# Gondola_Sail_electronics_M4.net
KiCad netlist of a schematic drawn in EAGLE
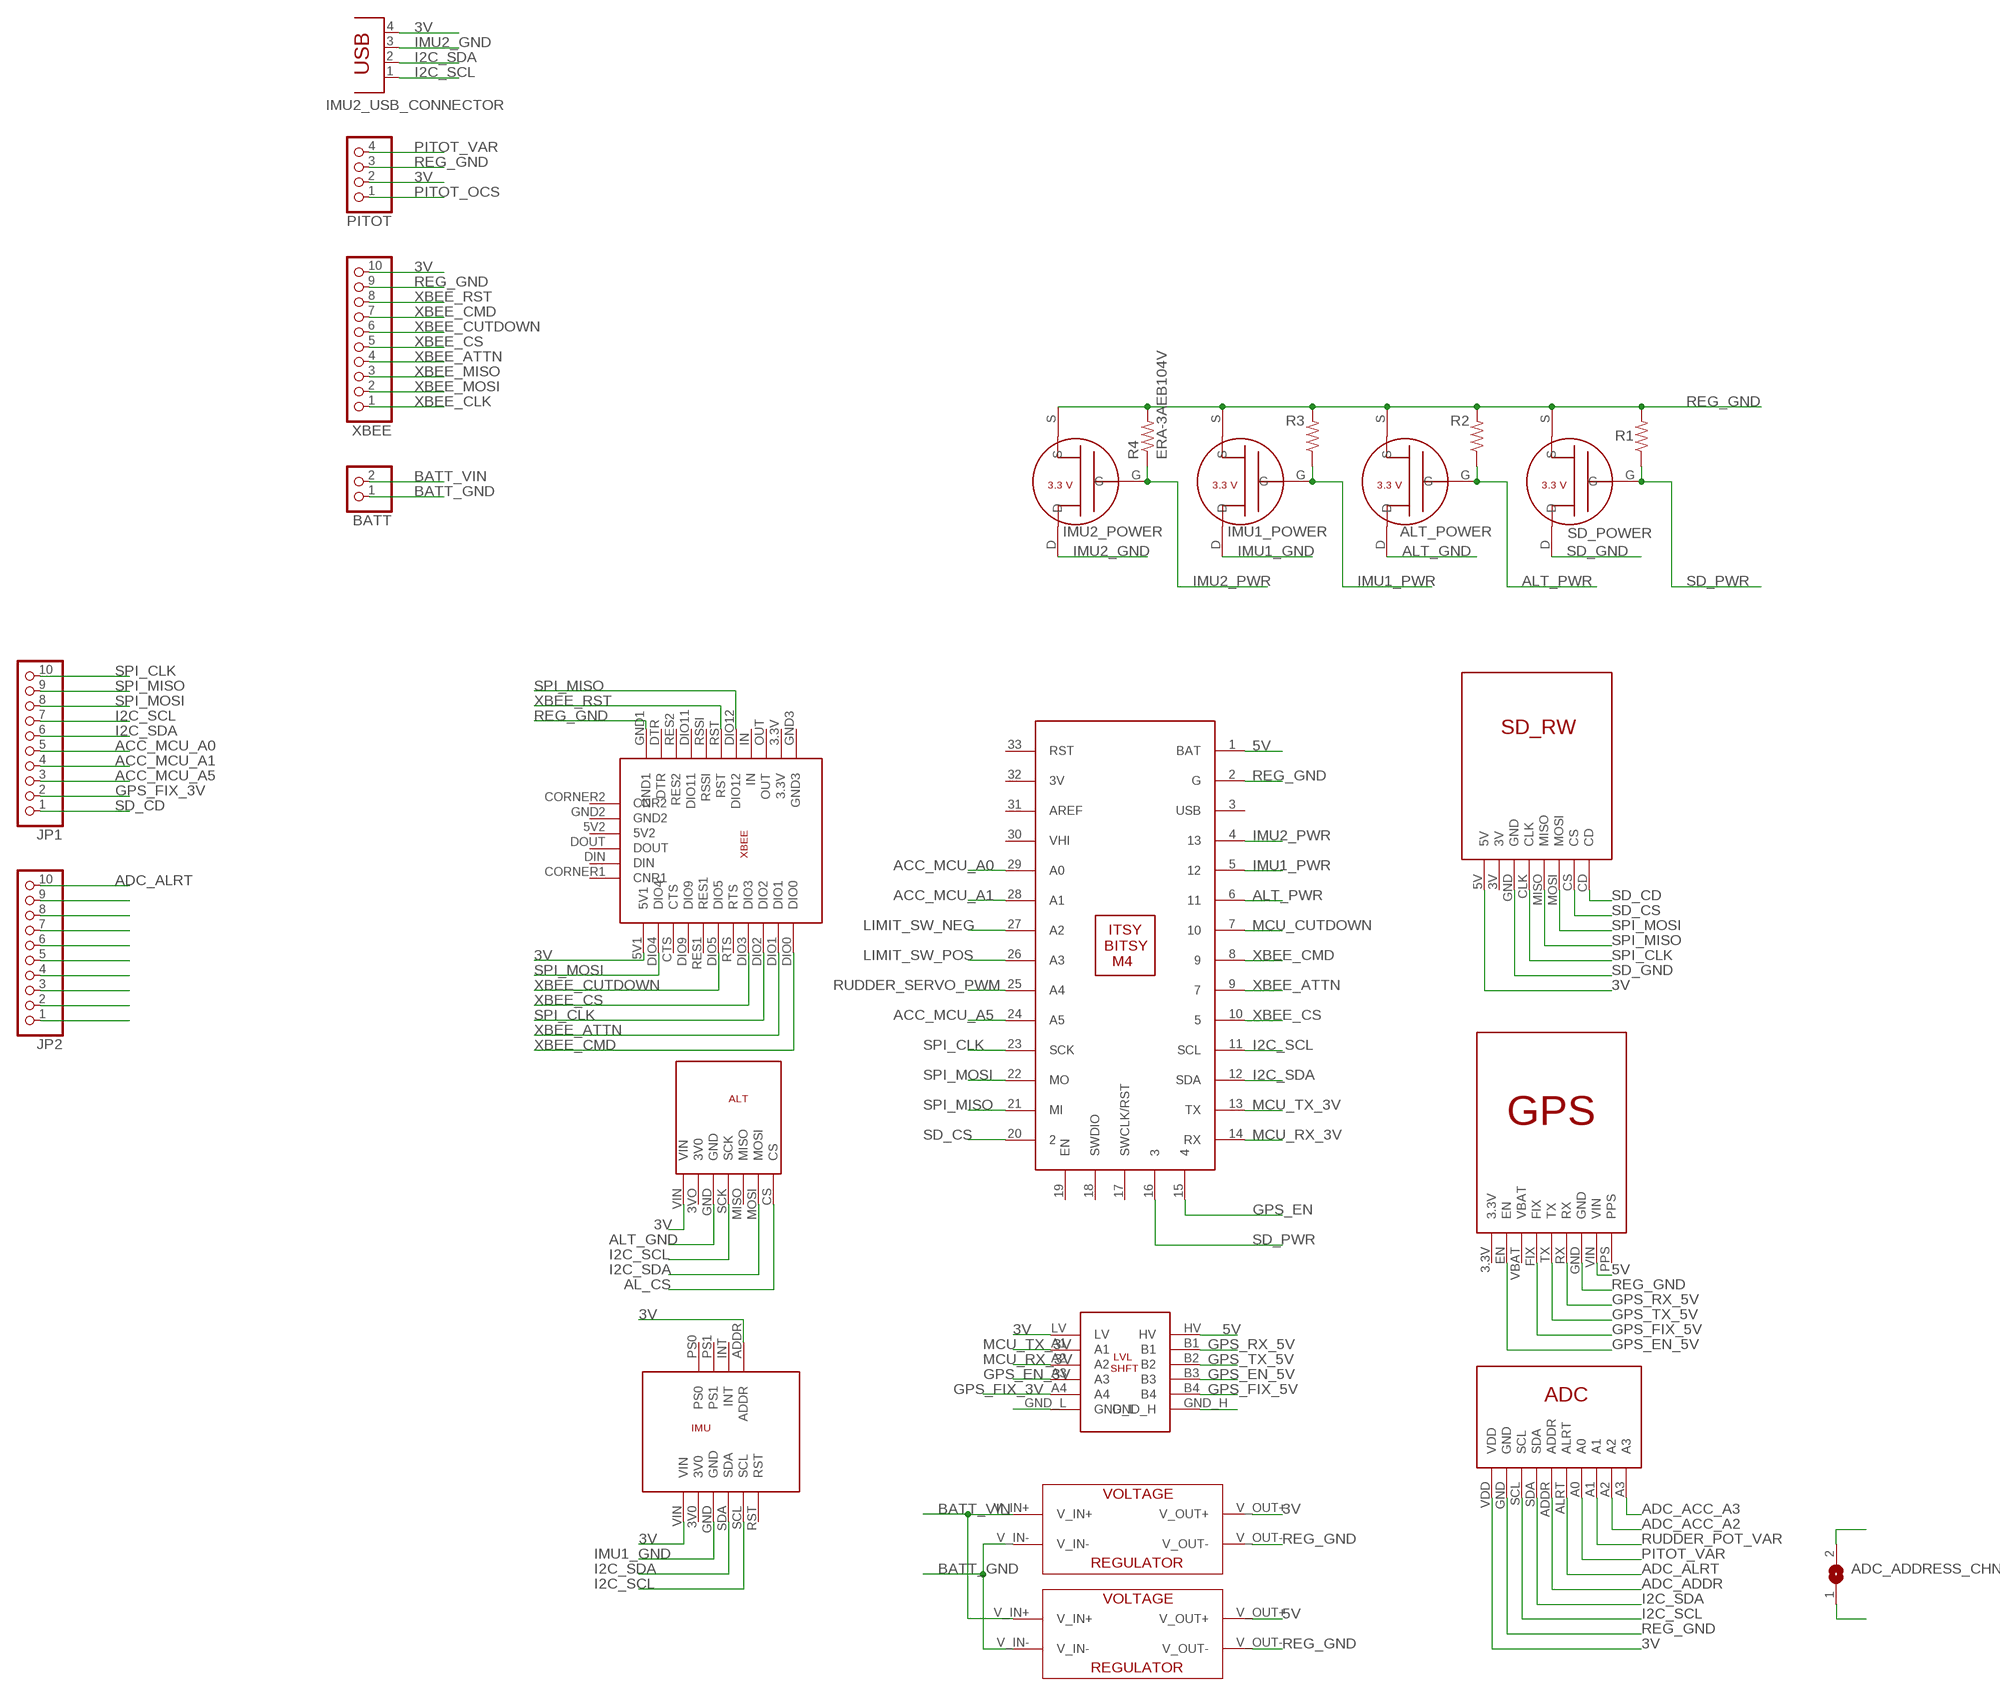
[diagram p0: schematic, sheet 1]

(export (version "E")
  (design (tool "Eeschema 10.0.6"))
  (components
    (comp (ref "3V_REG")
      (value "3V/5V_REGULATOR")
      (footprint "eagle-import:5V_3V_REGULATOR")
      (libsource (lib "eagle-import") (part "3V/5V_REGULATOR"))
    )
    (comp (ref "5V_REG")
      (value "3V/5V_REGULATOR")
      (footprint "eagle-import:5V_3V_REGULATOR")
      (libsource (lib "eagle-import") (part "3V/5V_REGULATOR"))
    )
    (comp (ref "ADC_ADDRESS_CHNG")
      (value "SJ")
      (footprint "eagle-import:SJ")
      (libsource (lib "eagle-import") (part "SJ"))
    )
    (comp (ref "ALT_POWER")
      (value "3.3V_NCH_FET")
      (footprint "eagle-import:3.3VTRANSISTOR")
      (libsource (lib "eagle-import") (part "3.3V_NCH_FET"))
    )
    (comp (ref "BATT")
      (value "PINHD-1X2/90")
      (footprint "eagle-import:1X02_90")
      (libsource (lib "eagle-import") (part "PINHD-1X2/90"))
    )
    (comp (ref "IMU1")
      (value "BNO055")
      (footprint "eagle-import:BNO055")
      (libsource (lib "eagle-import") (part "BNO055"))
    )
    (comp (ref "IMU1_POWER")
      (value "3.3V_NCH_FET")
      (footprint "eagle-import:3.3VTRANSISTOR")
      (libsource (lib "eagle-import") (part "3.3V_NCH_FET"))
    )
    (comp (ref "IMU2_POWER")
      (value "3.3V_NCH_FET")
      (footprint "eagle-import:3.3VTRANSISTOR")
      (libsource (lib "eagle-import") (part "3.3V_NCH_FET"))
    )
    (comp (ref "IMU2_USB_CONNECTOR")
      (value "PN87520")
      (footprint "eagle-import:PN87520")
      (libsource (lib "eagle-import") (part "PN87520"))
    )
    (comp (ref "JP1")
      (value "PINHD-1X10/90")
      (footprint "eagle-import:1X10_90")
      (libsource (lib "eagle-import") (part "PINHD-1X10/90"))
    )
    (comp (ref "JP2")
      (value "PINHD-1X10/90")
      (footprint "eagle-import:1X10_90")
      (libsource (lib "eagle-import") (part "PINHD-1X10/90"))
    )
    (comp (ref "PITOT")
      (value "PINHD-1X4/90")
      (footprint "eagle-import:1X04_90")
      (libsource (lib "eagle-import") (part "PINHD-1X4/90"))
    )
    (comp (ref "R1")
      (value "ERA-3AEB104V")
      (footprint "eagle-import:RESC1608X55")
      (fields (field (name "DIGI-KEY_PART_NUMBER") "P100KDBCT-ND") (field (name "MF") "Panasonic"))
      (libsource (lib "eagle-import") (part "ERA-3AEB104V"))
    )
    (comp (ref "R2")
      (value "ERA-3AEB104V")
      (footprint "eagle-import:RESC1608X55")
      (fields (field (name "DIGI-KEY_PART_NUMBER") "P100KDBCT-ND") (field (name "MF") "Panasonic"))
      (libsource (lib "eagle-import") (part "ERA-3AEB104V"))
    )
    (comp (ref "R3")
      (value "ERA-3AEB104V")
      (footprint "eagle-import:RESC1608X55")
      (fields (field (name "DIGI-KEY_PART_NUMBER") "P100KDBCT-ND") (field (name "MF") "Panasonic"))
      (libsource (lib "eagle-import") (part "ERA-3AEB104V"))
    )
    (comp (ref "R4")
      (value "ERA-3AEB104V")
      (footprint "eagle-import:RESC1608X55")
      (fields (field (name "DIGI-KEY_PART_NUMBER") "P100KDBCT-ND") (field (name "MF") "Panasonic"))
      (libsource (lib "eagle-import") (part "ERA-3AEB104V"))
    )
    (comp (ref "SD_POWER")
      (value "3.3V_NCH_FET")
      (footprint "eagle-import:3.3VTRANSISTOR")
      (libsource (lib "eagle-import") (part "3.3V_NCH_FET"))
    )
    (comp (ref "U$1")
      (value "ADAFRUIT_GPS")
      (footprint "eagle-import:ADAFRUIT_GPS")
      (libsource (lib "eagle-import") (part "ADAFRUIT_GPS"))
    )
    (comp (ref "U$2")
      (value "ADAFRUI_SD_RW")
      (footprint "eagle-import:ADAFRUIT_SD_RW")
      (libsource (lib "eagle-import") (part "ADAFRUI_SD_RW"))
    )
    (comp (ref "U$3")
      (value "ADS1115")
      (footprint "eagle-import:ADS1115")
      (libsource (lib "eagle-import") (part "ADS1115"))
    )
    (comp (ref "U$4")
      (value "BME280")
      (footprint "eagle-import:BME280")
      (libsource (lib "eagle-import") (part "BME280"))
    )
    (comp (ref "U$6")
      (value "BSS138_LVLSHIFT")
      (footprint "eagle-import:BSS138_LEVELSHIFT")
      (libsource (lib "eagle-import") (part "BSS138_LVLSHIFT"))
    )
    (comp (ref "U$7")
      (value "XBEE_XPLORER_REG")
      (footprint "eagle-import:XBEE_EXPLORER_REG'D")
      (libsource (lib "eagle-import") (part "XBEE_XPLORER_REG"))
    )
    (comp (ref "U$8")
      (value "ITSY_BITSY_M4")
      (footprint "eagle-import:ITSY_BITSY_M4")
      (libsource (lib "eagle-import") (part "ITSY_BITSY_M4"))
    )
    (comp (ref "XBEE")
      (value "PINHD-1X10/90")
      (footprint "eagle-import:1X10_90")
      (libsource (lib "eagle-import") (part "PINHD-1X10/90"))
    )
  )
  (nets
    (net (code "1") (name "/3V") (class "Default")
      (node (ref "3V_REG") (pin "V_OUT+") (pinfunction "V_OUT+_V_OUT+") (pintype "bidirectional"))
      (node (ref "IMU1") (pin "ADDR") (pinfunction "ADDR_ADDR") (pintype "bidirectional"))
      (node (ref "IMU1") (pin "VIN") (pinfunction "VIN_VIN") (pintype "bidirectional"))
      (node (ref "IMU2_USB_CONNECTOR") (pin "4") (pinfunction "4_4") (pintype "passive"))
      (node (ref "PITOT") (pin "2") (pinfunction "2_2") (pintype "passive"))
      (node (ref "U$2") (pin "5V") (pinfunction "5V_5V") (pintype "bidirectional"))
      (node (ref "U$3") (pin "VDD") (pinfunction "VDD_VDD") (pintype "bidirectional"))
      (node (ref "U$4") (pin "VIN") (pinfunction "VIN_VIN") (pintype "bidirectional"))
      (node (ref "U$6") (pin "LV") (pinfunction "LV_LV") (pintype "bidirectional"))
      (node (ref "U$7") (pin "5V1") (pinfunction "5V1_5V1") (pintype "bidirectional"))
      (node (ref "XBEE") (pin "10") (pinfunction "10_10") (pintype "passive"))
    )
    (net (code "2") (name "/5V") (class "Default")
      (node (ref "5V_REG") (pin "V_OUT+") (pinfunction "V_OUT+_V_OUT+") (pintype "bidirectional"))
      (node (ref "U$1") (pin "VIN") (pinfunction "VIN_VIN") (pintype "bidirectional"))
      (node (ref "U$6") (pin "HV") (pinfunction "HV_HV") (pintype "bidirectional"))
      (node (ref "U$8") (pin "1") (pinfunction "BAT_1") (pintype "output"))
    )
    (net (code "3") (name "/ACC_MCU_A0") (class "Default")
      (node (ref "JP1") (pin "5") (pinfunction "5_5") (pintype "passive"))
      (node (ref "U$8") (pin "29") (pinfunction "A0_29") (pintype "bidirectional"))
    )
    (net (code "4") (name "/ACC_MCU_A1") (class "Default")
      (node (ref "JP1") (pin "4") (pinfunction "4_4") (pintype "passive"))
      (node (ref "U$8") (pin "28") (pinfunction "A1_28") (pintype "bidirectional"))
    )
    (net (code "5") (name "/ACC_MCU_A5") (class "Default")
      (node (ref "JP1") (pin "3") (pinfunction "3_3") (pintype "passive"))
      (node (ref "U$8") (pin "24") (pinfunction "A5_24") (pintype "bidirectional"))
    )
    (net (code "6") (name "/ADC_ACC_A2") (class "Default")
      (node (ref "U$3") (pin "A2") (pinfunction "A2_A2") (pintype "bidirectional"))
    )
    (net (code "7") (name "/ADC_ACC_A3") (class "Default")
      (node (ref "U$3") (pin "A3") (pinfunction "A3_A3") (pintype "bidirectional"))
    )
    (net (code "8") (name "/ADC_ADDR") (class "Default")
      (node (ref "U$3") (pin "ADDR") (pinfunction "ADDR_ADDR") (pintype "bidirectional"))
    )
    (net (code "9") (name "/ADC_ALRT") (class "Default")
      (node (ref "JP2") (pin "10") (pinfunction "10_10") (pintype "passive"))
      (node (ref "U$3") (pin "ALRT") (pinfunction "ALRT_ALRT") (pintype "bidirectional"))
    )
    (net (code "10") (name "/ALT_GND") (class "Default")
      (node (ref "ALT_POWER") (pin "D") (pinfunction "D_D") (pintype "bidirectional"))
      (node (ref "U$4") (pin "GND") (pinfunction "GND_GND") (pintype "bidirectional"))
    )
    (net (code "11") (name "/ALT_PWR") (class "Default")
      (node (ref "ALT_POWER") (pin "G") (pinfunction "G_G") (pintype "bidirectional"))
      (node (ref "R2") (pin "1") (pinfunction "1_1") (pintype "passive"))
      (node (ref "U$8") (pin "6") (pinfunction "11_6") (pintype "bidirectional"))
    )
    (net (code "12") (name "/AL_CS") (class "Default")
      (node (ref "U$4") (pin "CS") (pinfunction "CS_CS") (pintype "bidirectional"))
    )
    (net (code "13") (name "/BATT_GND") (class "Default")
      (node (ref "3V_REG") (pin "V_IN-") (pinfunction "V_IN-_V_IN-") (pintype "bidirectional"))
      (node (ref "5V_REG") (pin "V_IN-") (pinfunction "V_IN-_V_IN-") (pintype "bidirectional"))
      (node (ref "BATT") (pin "1") (pinfunction "1_1") (pintype "passive"))
    )
    (net (code "14") (name "/BATT_VIN") (class "Default")
      (node (ref "3V_REG") (pin "V_IN+") (pinfunction "V_IN+_V_IN+") (pintype "bidirectional"))
      (node (ref "5V_REG") (pin "V_IN+") (pinfunction "V_IN+_V_IN+") (pintype "bidirectional"))
      (node (ref "BATT") (pin "2") (pinfunction "2_2") (pintype "passive"))
    )
    (net (code "15") (name "/GPS_EN") (class "Default")
      (node (ref "U$8") (pin "15") (pinfunction "4_15") (pintype "bidirectional"))
    )
    (net (code "16") (name "/GPS_EN_3V") (class "Default")
      (node (ref "U$6") (pin "A3") (pinfunction "A3_A3") (pintype "bidirectional"))
    )
    (net (code "17") (name "/GPS_EN_5V") (class "Default")
      (node (ref "U$1") (pin "EN") (pinfunction "EN_EN") (pintype "bidirectional"))
      (node (ref "U$6") (pin "B3") (pinfunction "B3_B3") (pintype "bidirectional"))
    )
    (net (code "18") (name "/GPS_FIX_3V") (class "Default")
      (node (ref "JP1") (pin "2") (pinfunction "2_2") (pintype "passive"))
      (node (ref "U$6") (pin "A4") (pinfunction "A4_A4") (pintype "bidirectional"))
    )
    (net (code "19") (name "/GPS_FIX_5V") (class "Default")
      (node (ref "U$1") (pin "FIX") (pinfunction "FIX_FIX") (pintype "bidirectional"))
      (node (ref "U$6") (pin "B4") (pinfunction "B4_B4") (pintype "bidirectional"))
    )
    (net (code "20") (name "/GPS_RX_5V") (class "Default")
      (node (ref "U$1") (pin "RX") (pinfunction "RX_RX") (pintype "bidirectional"))
      (node (ref "U$6") (pin "B1") (pinfunction "B1_B1") (pintype "bidirectional"))
    )
    (net (code "21") (name "/GPS_TX_5V") (class "Default")
      (node (ref "U$1") (pin "TX") (pinfunction "TX_TX") (pintype "bidirectional"))
      (node (ref "U$6") (pin "B2") (pinfunction "B2_B2") (pintype "bidirectional"))
    )
    (net (code "22") (name "/I2C_SCL") (class "Default")
      (node (ref "IMU1") (pin "SCL") (pinfunction "SCL_SCL") (pintype "bidirectional"))
      (node (ref "IMU2_USB_CONNECTOR") (pin "1") (pinfunction "1_1") (pintype "passive"))
      (node (ref "JP1") (pin "7") (pinfunction "7_7") (pintype "passive"))
      (node (ref "U$3") (pin "SCL") (pinfunction "SCL_SCL") (pintype "bidirectional"))
      (node (ref "U$4") (pin "SCK") (pinfunction "SCK_SCK") (pintype "bidirectional"))
      (node (ref "U$8") (pin "11") (pinfunction "SCL_11") (pintype "bidirectional"))
    )
    (net (code "23") (name "/I2C_SDA") (class "Default")
      (node (ref "IMU1") (pin "SDA") (pinfunction "SDA_SDA") (pintype "bidirectional"))
      (node (ref "IMU2_USB_CONNECTOR") (pin "2") (pinfunction "2_2") (pintype "passive"))
      (node (ref "JP1") (pin "6") (pinfunction "6_6") (pintype "passive"))
      (node (ref "U$3") (pin "SDA") (pinfunction "SDA_SDA") (pintype "bidirectional"))
      (node (ref "U$4") (pin "MOSI") (pinfunction "MOSI_MOSI") (pintype "bidirectional"))
      (node (ref "U$8") (pin "12") (pinfunction "SDA_12") (pintype "bidirectional"))
    )
    (net (code "24") (name "/IMU1_GND") (class "Default")
      (node (ref "IMU1") (pin "GND") (pinfunction "GND_GND") (pintype "bidirectional"))
      (node (ref "IMU1_POWER") (pin "D") (pinfunction "D_D") (pintype "bidirectional"))
    )
    (net (code "25") (name "/IMU1_PWR") (class "Default")
      (node (ref "IMU1_POWER") (pin "G") (pinfunction "G_G") (pintype "bidirectional"))
      (node (ref "R3") (pin "1") (pinfunction "1_1") (pintype "passive"))
      (node (ref "U$8") (pin "5") (pinfunction "12_5") (pintype "bidirectional"))
    )
    (net (code "26") (name "/IMU2_GND") (class "Default")
      (node (ref "IMU2_POWER") (pin "D") (pinfunction "D_D") (pintype "bidirectional"))
      (node (ref "IMU2_USB_CONNECTOR") (pin "3") (pinfunction "3_3") (pintype "passive"))
    )
    (net (code "27") (name "/IMU2_PWR") (class "Default")
      (node (ref "IMU2_POWER") (pin "G") (pinfunction "G_G") (pintype "bidirectional"))
      (node (ref "R4") (pin "1") (pinfunction "1_1") (pintype "passive"))
      (node (ref "U$8") (pin "4") (pinfunction "13_4") (pintype "bidirectional"))
    )
    (net (code "28") (name "/LIMIT_SW_NEG") (class "Default")
      (node (ref "U$8") (pin "27") (pinfunction "A2_27") (pintype "bidirectional"))
    )
    (net (code "29") (name "/LIMIT_SW_POS") (class "Default")
      (node (ref "U$8") (pin "26") (pinfunction "A3_26") (pintype "bidirectional"))
    )
    (net (code "30") (name "/MCU_CUTDOWN") (class "Default")
      (node (ref "U$8") (pin "7") (pinfunction "10_7") (pintype "bidirectional"))
    )
    (net (code "31") (name "/MCU_RX_3V") (class "Default")
      (node (ref "U$6") (pin "A2") (pinfunction "A2_A2") (pintype "bidirectional"))
      (node (ref "U$8") (pin "14") (pinfunction "RX_14") (pintype "bidirectional"))
    )
    (net (code "32") (name "/MCU_TX_3V") (class "Default")
      (node (ref "U$6") (pin "A1") (pinfunction "A1_A1") (pintype "bidirectional"))
      (node (ref "U$8") (pin "13") (pinfunction "TX_13") (pintype "bidirectional"))
    )
    (net (code "33") (name "/PITOT_OCS") (class "Default")
      (node (ref "PITOT") (pin "1") (pinfunction "1_1") (pintype "passive"))
    )
    (net (code "34") (name "/PITOT_VAR") (class "Default")
      (node (ref "PITOT") (pin "4") (pinfunction "4_4") (pintype "passive"))
      (node (ref "U$3") (pin "A0") (pinfunction "A0_A0") (pintype "bidirectional"))
    )
    (net (code "35") (name "/REG_GND") (class "Default")
      (node (ref "3V_REG") (pin "V_OUT-") (pinfunction "V_OUT-_V_OUT-") (pintype "bidirectional"))
      (node (ref "5V_REG") (pin "V_OUT-") (pinfunction "V_OUT-_V_OUT-") (pintype "bidirectional"))
      (node (ref "ALT_POWER") (pin "S") (pinfunction "S_S") (pintype "bidirectional"))
      (node (ref "IMU1_POWER") (pin "S") (pinfunction "S_S") (pintype "bidirectional"))
      (node (ref "IMU2_POWER") (pin "S") (pinfunction "S_S") (pintype "bidirectional"))
      (node (ref "PITOT") (pin "3") (pinfunction "3_3") (pintype "passive"))
      (node (ref "R1") (pin "2") (pinfunction "2_2") (pintype "passive"))
      (node (ref "R2") (pin "2") (pinfunction "2_2") (pintype "passive"))
      (node (ref "R3") (pin "2") (pinfunction "2_2") (pintype "passive"))
      (node (ref "R4") (pin "2") (pinfunction "2_2") (pintype "passive"))
      (node (ref "SD_POWER") (pin "S") (pinfunction "S_S") (pintype "bidirectional"))
      (node (ref "U$1") (pin "GND") (pinfunction "GND_GND") (pintype "bidirectional"))
      (node (ref "U$3") (pin "GND") (pinfunction "GND_GND") (pintype "bidirectional"))
      (node (ref "U$7") (pin "GND1") (pinfunction "GND1_GND1") (pintype "bidirectional"))
      (node (ref "U$8") (pin "2") (pinfunction "G_2") (pintype "bidirectional"))
      (node (ref "XBEE") (pin "9") (pinfunction "9_9") (pintype "passive"))
    )
    (net (code "36") (name "/RUDDER_POT_VAR") (class "Default")
      (node (ref "U$3") (pin "A1") (pinfunction "A1_A1") (pintype "bidirectional"))
    )
    (net (code "37") (name "/RUDDER_SERVO_PWM") (class "Default")
      (node (ref "U$8") (pin "25") (pinfunction "A4_25") (pintype "bidirectional"))
    )
    (net (code "38") (name "/SD_CD") (class "Default")
      (node (ref "JP1") (pin "1") (pinfunction "1_1") (pintype "passive"))
      (node (ref "U$2") (pin "CD") (pinfunction "CD_CD") (pintype "bidirectional"))
    )
    (net (code "39") (name "/SD_CS") (class "Default")
      (node (ref "U$2") (pin "CS") (pinfunction "CS_CS") (pintype "bidirectional"))
      (node (ref "U$8") (pin "20") (pinfunction "2_20") (pintype "bidirectional"))
    )
    (net (code "40") (name "/SD_GND") (class "Default")
      (node (ref "SD_POWER") (pin "D") (pinfunction "D_D") (pintype "bidirectional"))
      (node (ref "U$2") (pin "GND") (pinfunction "GND_GND") (pintype "bidirectional"))
    )
    (net (code "41") (name "/SD_PWR") (class "Default")
      (node (ref "R1") (pin "1") (pinfunction "1_1") (pintype "passive"))
      (node (ref "SD_POWER") (pin "G") (pinfunction "G_G") (pintype "bidirectional"))
      (node (ref "U$8") (pin "16") (pinfunction "3_16") (pintype "bidirectional"))
    )
    (net (code "42") (name "/SPI_CLK") (class "Default")
      (node (ref "JP1") (pin "10") (pinfunction "10_10") (pintype "passive"))
      (node (ref "U$2") (pin "CLK") (pinfunction "CLK_CLK") (pintype "bidirectional"))
      (node (ref "U$7") (pin "DIO2") (pinfunction "DIO2_DIO2") (pintype "bidirectional"))
      (node (ref "U$8") (pin "23") (pinfunction "SCK_23") (pintype "bidirectional"))
    )
    (net (code "43") (name "/SPI_MISO") (class "Default")
      (node (ref "JP1") (pin "9") (pinfunction "9_9") (pintype "passive"))
      (node (ref "U$2") (pin "MISO") (pinfunction "MISO_MISO") (pintype "bidirectional"))
      (node (ref "U$7") (pin "DIO12") (pinfunction "DIO12_DIO12") (pintype "bidirectional"))
      (node (ref "U$8") (pin "21") (pinfunction "MI_21") (pintype "bidirectional"))
    )
    (net (code "44") (name "/SPI_MOSI") (class "Default")
      (node (ref "JP1") (pin "8") (pinfunction "8_8") (pintype "passive"))
      (node (ref "U$2") (pin "MOSI") (pinfunction "MOSI_MOSI") (pintype "bidirectional"))
      (node (ref "U$7") (pin "DIO4") (pinfunction "DIO4_DIO4") (pintype "bidirectional"))
      (node (ref "U$8") (pin "22") (pinfunction "MO_22") (pintype "bidirectional"))
    )
    (net (code "45") (name "/XBEE_ATTN") (class "Default")
      (node (ref "U$7") (pin "DIO1") (pinfunction "DIO1_DIO1") (pintype "bidirectional"))
      (node (ref "U$8") (pin "9") (pinfunction "7_9") (pintype "bidirectional"))
      (node (ref "XBEE") (pin "4") (pinfunction "4_4") (pintype "passive"))
    )
    (net (code "46") (name "/XBEE_CLK") (class "Default")
      (node (ref "XBEE") (pin "1") (pinfunction "1_1") (pintype "passive"))
    )
    (net (code "47") (name "/XBEE_CMD") (class "Default")
      (node (ref "U$7") (pin "DIO0") (pinfunction "DIO0_DIO0") (pintype "bidirectional"))
      (node (ref "U$8") (pin "8") (pinfunction "9_8") (pintype "bidirectional"))
      (node (ref "XBEE") (pin "7") (pinfunction "7_7") (pintype "passive"))
    )
    (net (code "48") (name "/XBEE_CS") (class "Default")
      (node (ref "U$7") (pin "DIO3") (pinfunction "DIO3_DIO3") (pintype "bidirectional"))
      (node (ref "U$8") (pin "10") (pinfunction "5_10") (pintype "bidirectional"))
      (node (ref "XBEE") (pin "5") (pinfunction "5_5") (pintype "passive"))
    )
    (net (code "49") (name "/XBEE_CUTDOWN") (class "Default")
      (node (ref "U$7") (pin "DIO5") (pinfunction "DIO5_DIO5") (pintype "bidirectional"))
      (node (ref "XBEE") (pin "6") (pinfunction "6_6") (pintype "passive"))
    )
    (net (code "50") (name "/XBEE_MISO") (class "Default")
      (node (ref "XBEE") (pin "3") (pinfunction "3_3") (pintype "passive"))
    )
    (net (code "51") (name "/XBEE_MOSI") (class "Default")
      (node (ref "XBEE") (pin "2") (pinfunction "2_2") (pintype "passive"))
    )
    (net (code "52") (name "/XBEE_RST") (class "Default")
      (node (ref "U$7") (pin "RST") (pinfunction "RST_RST") (pintype "bidirectional"))
      (node (ref "XBEE") (pin "8") (pinfunction "8_8") (pintype "passive"))
    )
    (net (code "53") (name "unconnected-(ADC_ADDRESS_CHNG-Pad1)") (class "Default")
      (node (ref "ADC_ADDRESS_CHNG") (pin "1") (pinfunction "1_1") (pintype "passive"))
    )
    (net (code "54") (name "unconnected-(ADC_ADDRESS_CHNG-Pad2)") (class "Default")
      (node (ref "ADC_ADDRESS_CHNG") (pin "2") (pinfunction "2_2") (pintype "passive"))
    )
    (net (code "55") (name "unconnected-(IMU1-Pad3V0)") (class "Default")
      (node (ref "IMU1") (pin "3V0") (pinfunction "3V0_3V0") (pintype "bidirectional"))
    )
    (net (code "56") (name "unconnected-(IMU1-PadINT)") (class "Default")
      (node (ref "IMU1") (pin "INT") (pinfunction "INT_INT") (pintype "bidirectional"))
    )
    (net (code "57") (name "unconnected-(IMU1-PadPS0)") (class "Default")
      (node (ref "IMU1") (pin "PS0") (pinfunction "PS0_PS0") (pintype "bidirectional"))
    )
    (net (code "58") (name "unconnected-(IMU1-PadPS1)") (class "Default")
      (node (ref "IMU1") (pin "PS1") (pinfunction "PS1_PS1") (pintype "bidirectional"))
    )
    (net (code "59") (name "unconnected-(IMU1-PadRST)") (class "Default")
      (node (ref "IMU1") (pin "RST") (pinfunction "RST_RST") (pintype "bidirectional"))
    )
    (net (code "60") (name "unconnected-(JP2-Pad1)") (class "Default")
      (node (ref "JP2") (pin "1") (pinfunction "1_1") (pintype "passive"))
    )
    (net (code "61") (name "unconnected-(JP2-Pad2)") (class "Default")
      (node (ref "JP2") (pin "2") (pinfunction "2_2") (pintype "passive"))
    )
    (net (code "62") (name "unconnected-(JP2-Pad3)") (class "Default")
      (node (ref "JP2") (pin "3") (pinfunction "3_3") (pintype "passive"))
    )
    (net (code "63") (name "unconnected-(JP2-Pad4)") (class "Default")
      (node (ref "JP2") (pin "4") (pinfunction "4_4") (pintype "passive"))
    )
    (net (code "64") (name "unconnected-(JP2-Pad5)") (class "Default")
      (node (ref "JP2") (pin "5") (pinfunction "5_5") (pintype "passive"))
    )
    (net (code "65") (name "unconnected-(JP2-Pad6)") (class "Default")
      (node (ref "JP2") (pin "6") (pinfunction "6_6") (pintype "passive"))
    )
    (net (code "66") (name "unconnected-(JP2-Pad7)") (class "Default")
      (node (ref "JP2") (pin "7") (pinfunction "7_7") (pintype "passive"))
    )
    (net (code "67") (name "unconnected-(JP2-Pad8)") (class "Default")
      (node (ref "JP2") (pin "8") (pinfunction "8_8") (pintype "passive"))
    )
    (net (code "68") (name "unconnected-(JP2-Pad9)") (class "Default")
      (node (ref "JP2") (pin "9") (pinfunction "9_9") (pintype "passive"))
    )
    (net (code "69") (name "unconnected-(U$1-Pad3.3V)") (class "Default")
      (node (ref "U$1") (pin "3.3V") (pinfunction "3.3V_3.3V") (pintype "bidirectional"))
    )
    (net (code "70") (name "unconnected-(U$1-PadPPS)") (class "Default")
      (node (ref "U$1") (pin "PPS") (pinfunction "PPS_PPS") (pintype "bidirectional"))
    )
    (net (code "71") (name "unconnected-(U$1-PadVBAT)") (class "Default")
      (node (ref "U$1") (pin "VBAT") (pinfunction "VBAT_VBAT") (pintype "bidirectional"))
    )
    (net (code "72") (name "unconnected-(U$2-Pad3V)") (class "Default")
      (node (ref "U$2") (pin "3V") (pinfunction "3V_3V") (pintype "bidirectional"))
    )
    (net (code "73") (name "unconnected-(U$4-3V0-Pad3VO)") (class "Default")
      (node (ref "U$4") (pin "3VO") (pinfunction "3V0_3VO") (pintype "bidirectional"))
    )
    (net (code "74") (name "unconnected-(U$4-PadMISO)") (class "Default")
      (node (ref "U$4") (pin "MISO") (pinfunction "MISO_MISO") (pintype "bidirectional"))
    )
    (net (code "75") (name "unconnected-(U$6-PadGND_H)") (class "Default")
      (node (ref "U$6") (pin "GND_H") (pinfunction "GND_H_GND_H") (pintype "bidirectional"))
    )
    (net (code "76") (name "unconnected-(U$6-PadGND_L)") (class "Default")
      (node (ref "U$6") (pin "GND_L") (pinfunction "GND_L_GND_L") (pintype "bidirectional"))
    )
    (net (code "77") (name "unconnected-(U$7-CNR1-PadCORNER1)") (class "Default")
      (node (ref "U$7") (pin "CORNER1") (pinfunction "CNR1_CORNER1") (pintype "bidirectional"))
    )
    (net (code "78") (name "unconnected-(U$7-CNR2-PadCORNER2)") (class "Default")
      (node (ref "U$7") (pin "CORNER2") (pinfunction "CNR2_CORNER2") (pintype "bidirectional"))
    )
    (net (code "79") (name "unconnected-(U$7-Pad3.3V)") (class "Default")
      (node (ref "U$7") (pin "3.3V") (pinfunction "3.3V_3.3V") (pintype "bidirectional"))
    )
    (net (code "80") (name "unconnected-(U$7-Pad5V2)") (class "Default")
      (node (ref "U$7") (pin "5V2") (pinfunction "5V2_5V2") (pintype "bidirectional"))
    )
    (net (code "81") (name "unconnected-(U$7-PadCTS)") (class "Default")
      (node (ref "U$7") (pin "CTS") (pinfunction "CTS_CTS") (pintype "bidirectional"))
    )
    (net (code "82") (name "unconnected-(U$7-PadDIN)") (class "Default")
      (node (ref "U$7") (pin "DIN") (pinfunction "DIN_DIN") (pintype "bidirectional"))
    )
    (net (code "83") (name "unconnected-(U$7-PadDIO9)") (class "Default")
      (node (ref "U$7") (pin "DIO9") (pinfunction "DIO9_DIO9") (pintype "bidirectional"))
    )
    (net (code "84") (name "unconnected-(U$7-PadDIO11)") (class "Default")
      (node (ref "U$7") (pin "DIO11") (pinfunction "DIO11_DIO11") (pintype "bidirectional"))
    )
    (net (code "85") (name "unconnected-(U$7-PadDOUT)") (class "Default")
      (node (ref "U$7") (pin "DOUT") (pinfunction "DOUT_DOUT") (pintype "bidirectional"))
    )
    (net (code "86") (name "unconnected-(U$7-PadDTR)") (class "Default")
      (node (ref "U$7") (pin "DTR") (pinfunction "DTR_DTR") (pintype "bidirectional"))
    )
    (net (code "87") (name "unconnected-(U$7-PadGND2)") (class "Default")
      (node (ref "U$7") (pin "GND2") (pinfunction "GND2_GND2") (pintype "bidirectional"))
    )
    (net (code "88") (name "unconnected-(U$7-PadGND3)") (class "Default")
      (node (ref "U$7") (pin "GND3") (pinfunction "GND3_GND3") (pintype "bidirectional"))
    )
    (net (code "89") (name "unconnected-(U$7-PadIN)") (class "Default")
      (node (ref "U$7") (pin "IN") (pinfunction "IN_IN") (pintype "bidirectional"))
    )
    (net (code "90") (name "unconnected-(U$7-PadOUT)") (class "Default")
      (node (ref "U$7") (pin "OUT") (pinfunction "OUT_OUT") (pintype "bidirectional"))
    )
    (net (code "91") (name "unconnected-(U$7-PadRES1)") (class "Default")
      (node (ref "U$7") (pin "RES1") (pinfunction "RES1_RES1") (pintype "bidirectional"))
    )
    (net (code "92") (name "unconnected-(U$7-PadRES2)") (class "Default")
      (node (ref "U$7") (pin "RES2") (pinfunction "RES2_RES2") (pintype "bidirectional"))
    )
    (net (code "93") (name "unconnected-(U$7-PadRSSI)") (class "Default")
      (node (ref "U$7") (pin "RSSI") (pinfunction "RSSI_RSSI") (pintype "bidirectional"))
    )
    (net (code "94") (name "unconnected-(U$7-PadRTS)") (class "Default")
      (node (ref "U$7") (pin "RTS") (pinfunction "RTS_RTS") (pintype "bidirectional"))
    )
    (net (code "95") (name "unconnected-(U$8-3V-Pad32)") (class "Default")
      (node (ref "U$8") (pin "32") (pinfunction "3V_32") (pintype "bidirectional"))
    )
    (net (code "96") (name "unconnected-(U$8-AREF-Pad31)") (class "Default")
      (node (ref "U$8") (pin "31") (pinfunction "AREF_31") (pintype "bidirectional"))
    )
    (net (code "97") (name "unconnected-(U$8-EN-Pad19)") (class "Default")
      (node (ref "U$8") (pin "19") (pinfunction "EN_19") (pintype "bidirectional"))
    )
    (net (code "98") (name "unconnected-(U$8-RST-Pad33)") (class "Default")
      (node (ref "U$8") (pin "33") (pinfunction "RST_33") (pintype "bidirectional"))
    )
    (net (code "99") (name "unconnected-(U$8-SWCLK{slash}RST-Pad17)") (class "Default")
      (node (ref "U$8") (pin "17") (pinfunction "SWCLK/RST_17") (pintype "bidirectional"))
    )
    (net (code "100") (name "unconnected-(U$8-SWDIO-Pad18)") (class "Default")
      (node (ref "U$8") (pin "18") (pinfunction "SWDIO_18") (pintype "bidirectional"))
    )
    (net (code "101") (name "unconnected-(U$8-USB-Pad3)") (class "Default")
      (node (ref "U$8") (pin "3") (pinfunction "USB_3") (pintype "bidirectional"))
    )
    (net (code "102") (name "unconnected-(U$8-VHI-Pad30)") (class "Default")
      (node (ref "U$8") (pin "30") (pinfunction "VHI_30") (pintype "bidirectional"))
    )
  )
)
